# geigerboardschematic.net
KiCad netlist of a schematic drawn in EasyEDA Pro
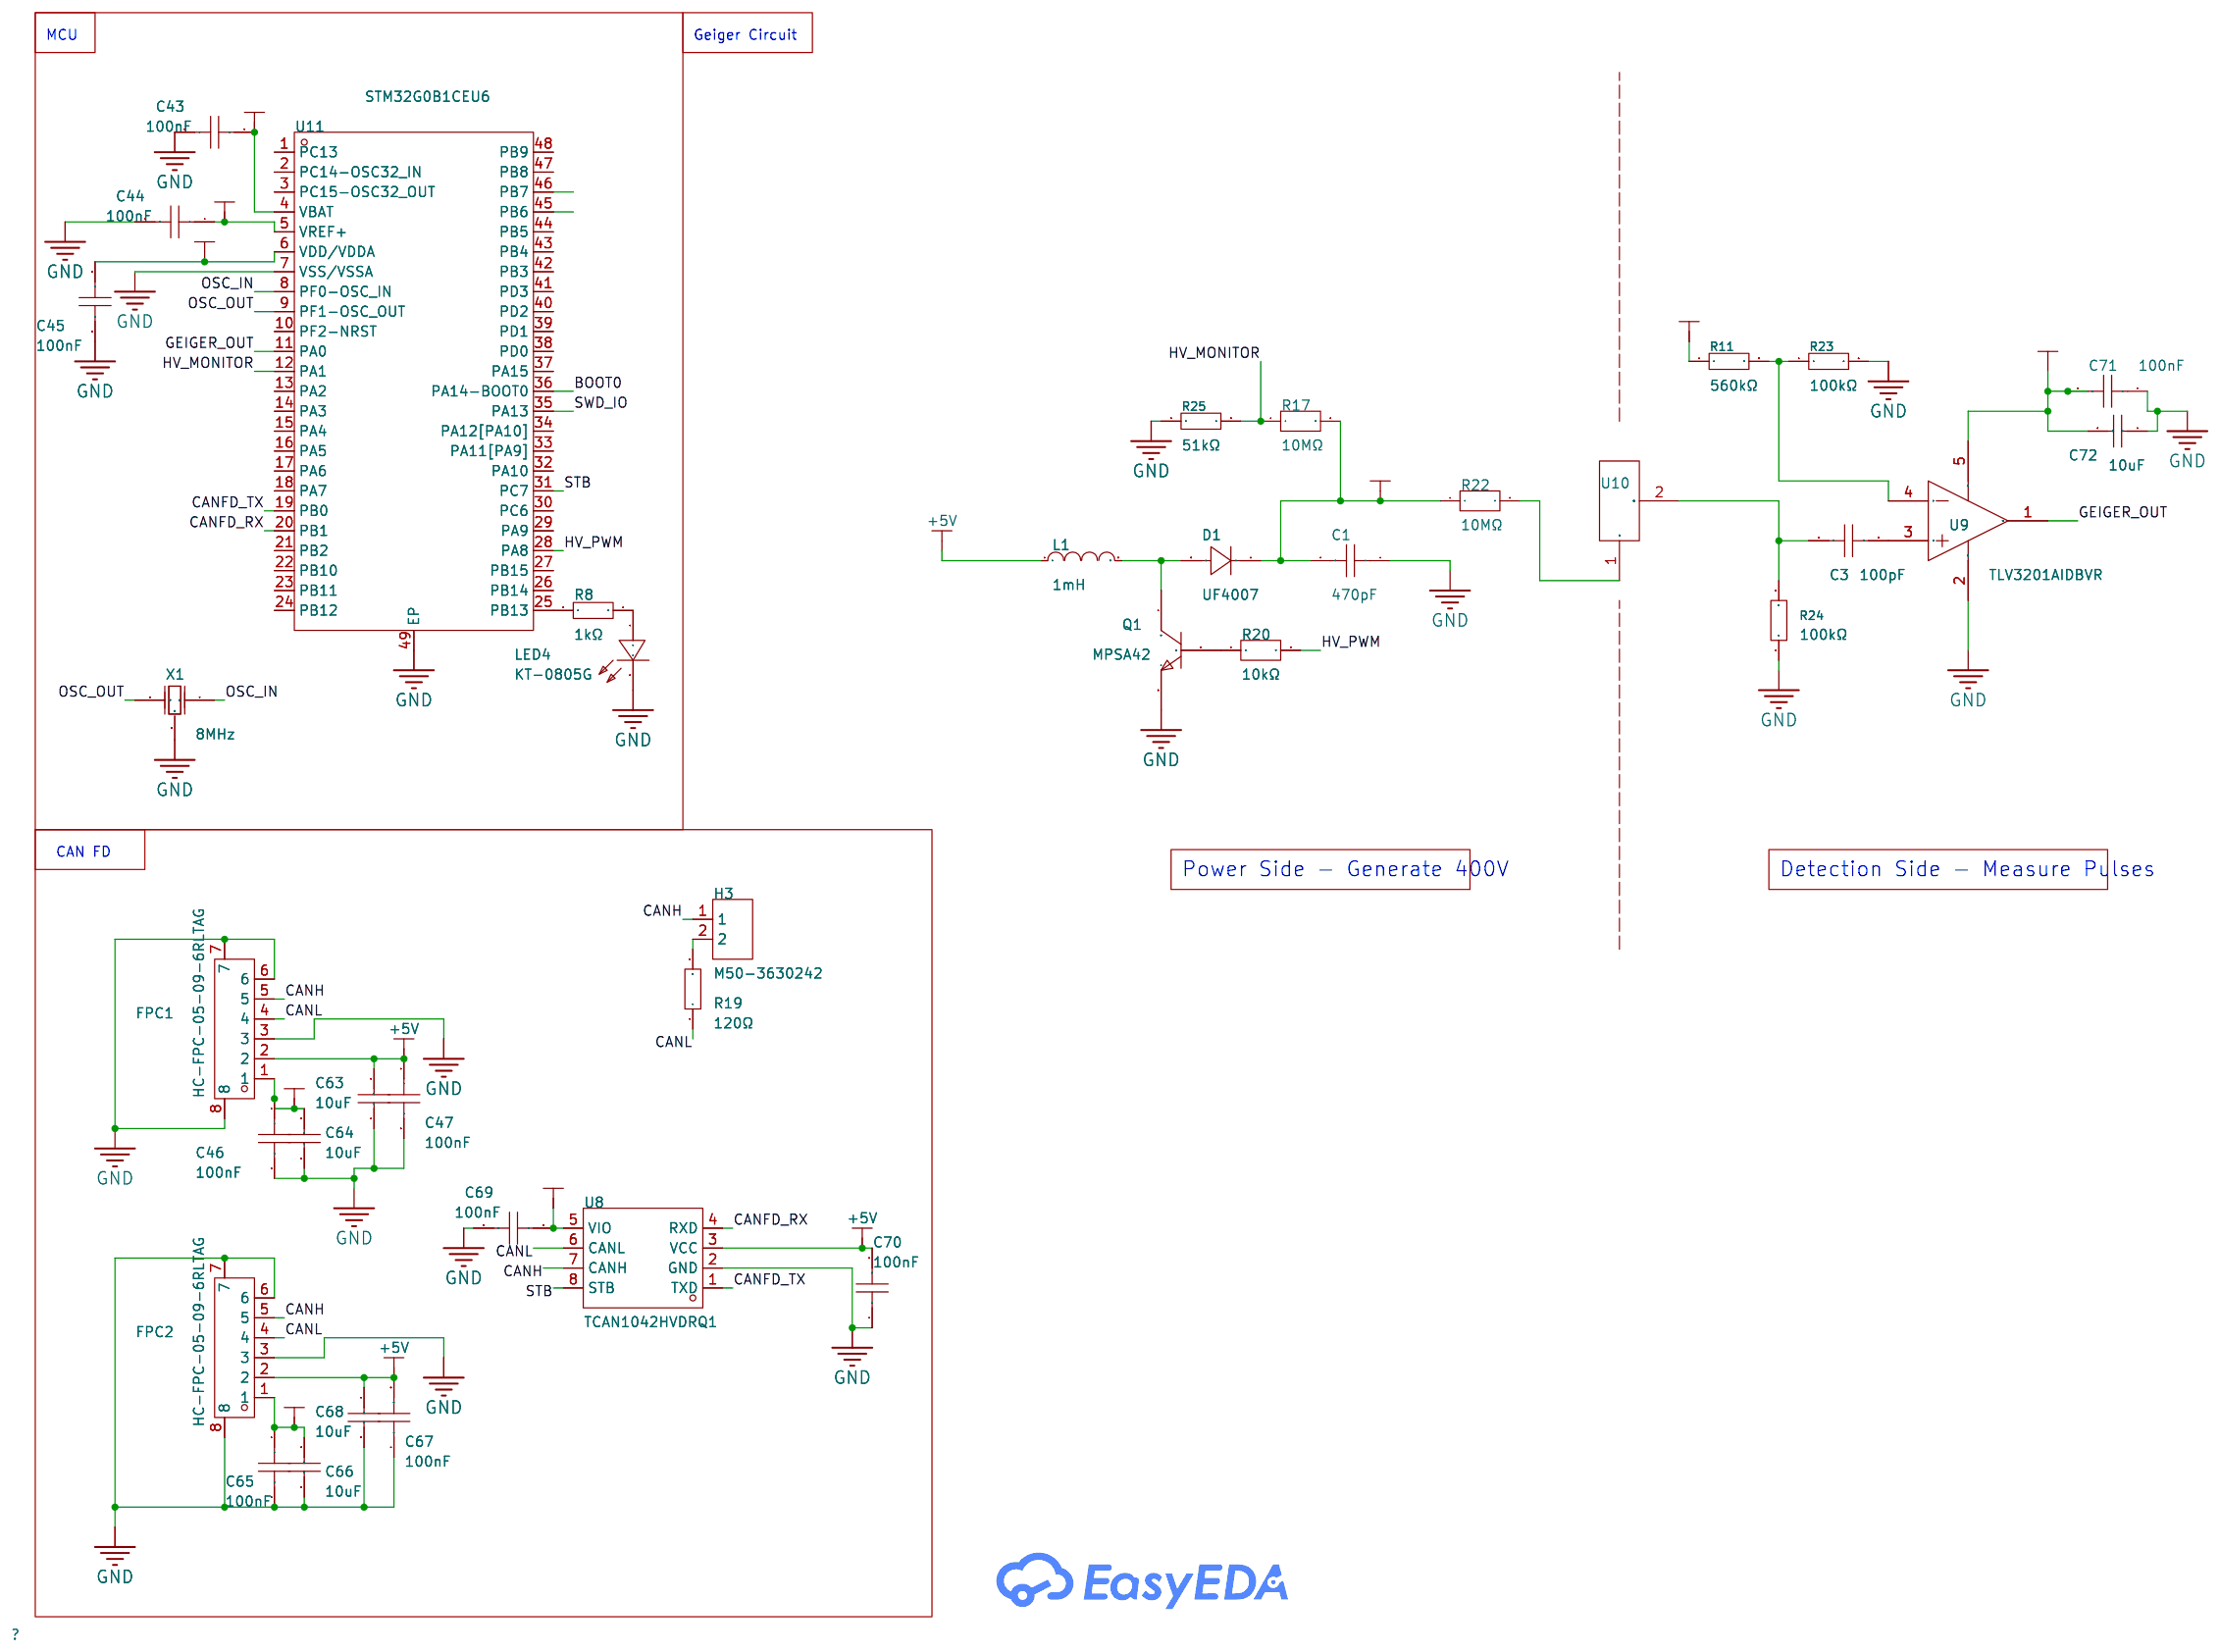
[diagram p0: schematic sheet]

(export (version "E")
  (design (tool "Eeschema 10.0.6"))
  (components
    (comp (ref "C1")
      (value "470pF")
      (footprint "easyedapro:C1111")
      (description "Capacitance:470pF Tolerance:±10% Tolerance:±10% Voltage Rating:630V Temperature Coefficient:C0G")
      (fields (field (name "Manufacturer Part") "VJ1111D471KXLAT") (field (name "Manufacturer") "VISHAY(威世)"))
      (libsource (lib "easyedapro") (part "VJ1111D471KXLAT"))
    )
    (comp (ref "C3")
      (value "100pF")
      (footprint "easyedapro:C1206")
      (fields (field (name "Manufacturer Part") "1206N101J631CT") (field (name "Manufacturer") "Walsin(华新科)"))
      (libsource (lib "easyedapro") (part "1206N101J631CT"))
    )
    (comp (ref "C43")
      (value "100nF")
      (footprint "easyedapro:C0402")
      (description "Capacitance:100nF Tolerance:±10% Tolerance:±10% Voltage Rating:16V Temperature Coefficient:X7R")
      (fields
        (field (name "Manufacturer Part") "CL05B104KO5NNNC")
        (field (name "Manufacturer") "SAMSUNG(三星)")
      )
      (libsource (lib "easyedapro") (part "CL05B104KO5NNNC"))
    )
    (comp (ref "C44")
      (value "100nF")
      (footprint "easyedapro:C0402")
      (description "Capacitance:100nF Tolerance:±10% Tolerance:±10% Voltage Rating:16V Temperature Coefficient:X7R")
      (fields
        (field (name "Manufacturer Part") "CL05B104KO5NNNC")
        (field (name "Manufacturer") "SAMSUNG(三星)")
      )
      (libsource (lib "easyedapro") (part "CL05B104KO5NNNC"))
    )
    (comp (ref "C45")
      (value "100nF")
      (footprint "easyedapro:C0402")
      (description "Capacitance:100nF Tolerance:±10% Tolerance:±10% Voltage Rating:16V Temperature Coefficient:X7R")
      (fields
        (field (name "Manufacturer Part") "CL05B104KO5NNNC")
        (field (name "Manufacturer") "SAMSUNG(三星)")
      )
      (libsource (lib "easyedapro") (part "CL05B104KO5NNNC"))
    )
    (comp (ref "C46")
      (value "100nF")
      (footprint "easyedapro:C0402")
      (description "Capacitance:100nF Tolerance:±10% Tolerance:±10% Voltage Rating:16V Temperature Coefficient:X7R")
      (fields
        (field (name "Manufacturer Part") "CL05B104KO5NNNC")
        (field (name "Manufacturer") "SAMSUNG(三星)")
      )
      (libsource (lib "easyedapro") (part "CL05B104KO5NNNC"))
    )
    (comp (ref "C47")
      (value "100nF")
      (footprint "easyedapro:C0402")
      (description "Capacitance:100nF Tolerance:±10% Tolerance:±10% Voltage Rating:16V Temperature Coefficient:X7R")
      (fields
        (field (name "Manufacturer Part") "CL05B104KO5NNNC")
        (field (name "Manufacturer") "SAMSUNG(三星)")
      )
      (libsource (lib "easyedapro") (part "CL05B104KO5NNNC"))
    )
    (comp (ref "C63")
      (value "10uF")
      (footprint "easyedapro:C0402")
      (description "Capacitance:10uF Tolerance:±20% Tolerance:±20% Voltage Rating:6.3V Temperature Coefficient:X5R")
      (fields
        (field (name "Manufacturer Part") "CL05A106MQ5NUNC")
        (field (name "Manufacturer") "SAMSUNG(三星)")
      )
      (libsource (lib "easyedapro") (part "CL05A106MQ5NUNC"))
    )
    (comp (ref "C64")
      (value "10uF")
      (footprint "easyedapro:C0402")
      (description "Capacitance:10uF Tolerance:±20% Tolerance:±20% Voltage Rating:6.3V Temperature Coefficient:X5R")
      (fields
        (field (name "Manufacturer Part") "CL05A106MQ5NUNC")
        (field (name "Manufacturer") "SAMSUNG(三星)")
      )
      (libsource (lib "easyedapro") (part "CL05A106MQ5NUNC"))
    )
    (comp (ref "C65")
      (value "100nF")
      (footprint "easyedapro:C0402")
      (description "Capacitance:100nF Tolerance:±10% Tolerance:±10% Voltage Rating:16V Temperature Coefficient:X7R")
      (fields
        (field (name "Manufacturer Part") "CL05B104KO5NNNC")
        (field (name "Manufacturer") "SAMSUNG(三星)")
      )
      (libsource (lib "easyedapro") (part "CL05B104KO5NNNC"))
    )
    (comp (ref "C66")
      (value "10uF")
      (footprint "easyedapro:C0402")
      (description "Capacitance:10uF Tolerance:±20% Tolerance:±20% Voltage Rating:6.3V Temperature Coefficient:X5R")
      (fields
        (field (name "Manufacturer Part") "CL05A106MQ5NUNC")
        (field (name "Manufacturer") "SAMSUNG(三星)")
      )
      (libsource (lib "easyedapro") (part "CL05A106MQ5NUNC"))
    )
    (comp (ref "C67")
      (value "100nF")
      (footprint "easyedapro:C0402")
      (description "Capacitance:100nF Tolerance:±10% Tolerance:±10% Voltage Rating:16V Temperature Coefficient:X7R")
      (fields
        (field (name "Manufacturer Part") "CL05B104KO5NNNC")
        (field (name "Manufacturer") "SAMSUNG(三星)")
      )
      (libsource (lib "easyedapro") (part "CL05B104KO5NNNC"))
    )
    (comp (ref "C68")
      (value "10uF")
      (footprint "easyedapro:C0402")
      (description "Capacitance:10uF Tolerance:±20% Tolerance:±20% Voltage Rating:6.3V Temperature Coefficient:X5R")
      (fields
        (field (name "Manufacturer Part") "CL05A106MQ5NUNC")
        (field (name "Manufacturer") "SAMSUNG(三星)")
      )
      (libsource (lib "easyedapro") (part "CL05A106MQ5NUNC"))
    )
    (comp (ref "C69")
      (value "100nF")
      (footprint "easyedapro:C0402")
      (description "Capacitance:100nF Tolerance:±10% Tolerance:±10% Voltage Rating:16V Temperature Coefficient:X7R")
      (fields
        (field (name "Manufacturer Part") "CL05B104KO5NNNC")
        (field (name "Manufacturer") "SAMSUNG(三星)")
      )
      (libsource (lib "easyedapro") (part "CL05B104KO5NNNC"))
    )
    (comp (ref "C70")
      (value "100nF")
      (footprint "easyedapro:C0402")
      (description "Capacitance:100nF Tolerance:±10% Tolerance:±10% Voltage Rating:16V Temperature Coefficient:X7R")
      (fields
        (field (name "Manufacturer Part") "CL05B104KO5NNNC")
        (field (name "Manufacturer") "SAMSUNG(三星)")
      )
      (libsource (lib "easyedapro") (part "CL05B104KO5NNNC"))
    )
    (comp (ref "C71")
      (value "100nF")
      (footprint "easyedapro:C0402")
      (description "Capacitance:100nF Tolerance:±10% Tolerance:±10% Voltage Rating:16V Temperature Coefficient:X7R")
      (fields
        (field (name "Manufacturer Part") "CL05B104KO5NNNC")
        (field (name "Manufacturer") "SAMSUNG(三星)")
      )
      (libsource (lib "easyedapro") (part "CL05B104KO5NNNC"))
    )
    (comp (ref "C72")
      (value "10uF")
      (footprint "easyedapro:C0402")
      (description "Capacitance:10uF Tolerance:±20% Tolerance:±20% Voltage Rating:6.3V Temperature Coefficient:X5R")
      (fields
        (field (name "Manufacturer Part") "CL05A106MQ5NUNC")
        (field (name "Manufacturer") "SAMSUNG(三星)")
      )
      (libsource (lib "easyedapro") (part "CL05A106MQ5NUNC"))
    )
    (comp (ref "D1")
      (value "UF4007")
      (footprint "easyedapro:DO-41_BD2.4-L4.7-P8.70-D0.9-RD")
      (fields (field (name "Manufacturer") "MDD(辰达半导体)"))
      (libsource (lib "easyedapro") (part "UF4007_C960666"))
    )
    (comp (ref "FPC1")
      (value "HC-FPC-05-09-6RLTAG")
      (footprint "easyedapro:FPC-SMD_6P-P0.50_HC-FPC-05-09-6RLTAG")
      (fields (field (name "Manufacturer") "HCTL(华灿天禄)"))
      (libsource (lib "easyedapro") (part "HC-FPC-05-09-6RLTAG"))
    )
    (comp (ref "FPC2")
      (value "HC-FPC-05-09-6RLTAG")
      (footprint "easyedapro:FPC-SMD_6P-P0.50_HC-FPC-05-09-6RLTAG")
      (fields (field (name "Manufacturer") "HCTL(华灿天禄)"))
      (libsource (lib "easyedapro") (part "HC-FPC-05-09-6RLTAG"))
    )
    (comp (ref "H3")
      (value "M50-3630242")
      (footprint "easyedapro:HDR-SMD_2P-P1.27_M50-3630242")
      (fields (field (name "Manufacturer") "Harwin"))
      (libsource (lib "easyedapro") (part "M50-3630242"))
    )
    (comp (ref "L1")
      (value "1mH")
      (footprint "easyedapro:IND-SMD_L5.0-W5.0_FNR50XXS")
      (fields (field (name "Manufacturer Part") "FNR5040S102MT") (field (name "Manufacturer") "cjiang(长江微电)"))
      (libsource (lib "easyedapro") (part "FNR5040S102MT"))
    )
    (comp (ref "LED4")
      (value "KT-0805G")
      (footprint "easyedapro:LED0805-R-RD")
      (fields (field (name "Manufacturer") "KENTO"))
      (libsource (lib "easyedapro") (part "0805G (Green)"))
    )
    (comp (ref "Q1")
      (value "MPSA42")
      (footprint "easyedapro:TO-92-3_L4.8-W3.7-P2.54-R")
      (fields (field (name "Manufacturer") "BLUE ROCKET(蓝箭)"))
      (libsource (lib "easyedapro") (part "MPSA42_C305411"))
    )
    (comp (ref "R8")
      (value "1kΩ")
      (footprint "easyedapro:R0402")
      (fields
        (field (name "Manufacturer Part") "0402WGF1001TCE")
        (field (name "Manufacturer") "UNI-ROYAL(厚声)")
      )
      (libsource (lib "easyedapro") (part "0402WGF1001TCE"))
    )
    (comp (ref "R11")
      (value "560kΩ")
      (footprint "easyedapro:R0402")
      (fields
        (field (name "Manufacturer Part") "0402WGF5603TCE")
        (field (name "Manufacturer") "UNI-ROYAL(厚声)")
      )
      (libsource (lib "easyedapro") (part "0402WGF5603TCE"))
    )
    (comp (ref "R17")
      (value "10MΩ")
      (footprint "easyedapro:R1206")
      (fields (field (name "Manufacturer Part") "KTR18EZPJ106") (field (name "Manufacturer") "ROHM(罗姆)"))
      (libsource (lib "easyedapro") (part "KTR18EZPJ106"))
    )
    (comp (ref "R19")
      (value "120Ω")
      (footprint "easyedapro:R0402")
      (fields
        (field (name "Manufacturer Part") "0402WGF1200TCE")
        (field (name "Manufacturer") "UNI-ROYAL(厚声)")
      )
      (libsource (lib "easyedapro") (part "0402WGF1200TCE"))
    )
    (comp (ref "R20")
      (value "10kΩ")
      (footprint "easyedapro:R0402")
      (fields (field (name "Manufacturer Part") "FRC0402J103 TS") (field (name "Manufacturer") "FOJAN(富捷)"))
      (libsource (lib "easyedapro") (part "FRC0402J103 TS"))
    )
    (comp (ref "R22")
      (value "10MΩ")
      (footprint "easyedapro:R1206")
      (fields (field (name "Manufacturer Part") "KTR18EZPJ106") (field (name "Manufacturer") "ROHM(罗姆)"))
      (libsource (lib "easyedapro") (part "KTR18EZPJ106"))
    )
    (comp (ref "R23")
      (value "100kΩ")
      (footprint "easyedapro:R0402")
      (fields
        (field (name "Manufacturer Part") "0402WGF1003TCE")
        (field (name "Manufacturer") "UNI-ROYAL(厚声)")
      )
      (libsource (lib "easyedapro") (part "0402WGF1003TCE"))
    )
    (comp (ref "R24")
      (value "100kΩ")
      (footprint "easyedapro:R0402")
      (fields
        (field (name "Manufacturer Part") "0402WGF1003TCE")
        (field (name "Manufacturer") "UNI-ROYAL(厚声)")
      )
      (libsource (lib "easyedapro") (part "0402WGF1003TCE"))
    )
    (comp (ref "R25")
      (value "51kΩ")
      (footprint "easyedapro:R0805")
      (fields
        (field (name "Manufacturer Part") "0805W8F5102T5E")
        (field (name "Manufacturer") "UNI-ROYAL(厚声)")
      )
      (libsource (lib "easyedapro") (part "0805W8F5102T5E"))
    )
    (comp (ref "U8")
      (value "TCAN1042HVDRQ1")
      (footprint "easyedapro:SOIC-8_L4.9-W3.9-P1.27-LS6.0-BL")
      (fields (field (name "Manufacturer") "TI(德州仪器)"))
      (libsource (lib "easyedapro") (part "TCAN1042HVDRQ1"))
    )
    (comp (ref "U9")
      (value "TLV3201AIDBVR")
      (footprint "easyedapro:SOT-23-5_L3.0-W1.7-P0.95-LS2.8-BR")
      (fields (field (name "Manufacturer") "TI(德州仪器)"))
      (libsource (lib "easyedapro") (part "TLV3201AIDBVR"))
    )
    (comp (ref "U10")
      (value "SBM-21")
      (footprint "easyedapro:SBM21")
      (libsource (lib "easyedapro") (part "SBM21"))
    )
    (comp (ref "U11")
      (value "STM32G0B1CEU6")
      (footprint "easyedapro:UFQFPN-48_L7.0-W7.0-P0.50-BL-EP")
      (fields (field (name "Manufacturer") "ST(意法半导体)"))
      (libsource (lib "easyedapro") (part "STM32G0B1CEU6"))
    )
    (comp (ref "X1")
      (value "8MHz")
      (footprint "easyedapro:OSC-SMD_3P-L3.2-W1.3-P1.20-L")
      (fields
        (field (name "Manufacturer Part") "CSTNE8M00GH5C000R0")
        (field (name "Manufacturer") "muRata(村田)")
      )
      (libsource (lib "easyedapro") (part "CSTNE8M00GH5C000R0"))
    )
  )
  (nets
    (net (code "1") (name "+5V") (class "Default")
      (node (ref "C47") (pin "1") (pinfunction "1_1") (pintype "unspecified"))
      (node (ref "C63") (pin "2") (pinfunction "2_2") (pintype "input"))
      (node (ref "C67") (pin "2") (pinfunction "2_2") (pintype "unspecified"))
      (node (ref "C68") (pin "1") (pinfunction "1_1") (pintype "input"))
      (node (ref "C70") (pin "2") (pinfunction "2_2") (pintype "unspecified"))
      (node (ref "FPC1") (pin "2") (pinfunction "2_2") (pintype "unspecified"))
      (node (ref "FPC2") (pin "2") (pinfunction "2_2") (pintype "unspecified"))
      (node (ref "L1") (pin "1") (pinfunction "1_1") (pintype "unspecified"))
      (node (ref "U8") (pin "3") (pinfunction "VCC_3") (pintype "unspecified"))
    )
    (net (code "2") (name "+400V") (class "Default")
      (node (ref "C1") (pin "2") (pinfunction "2_2") (pintype "unspecified"))
      (node (ref "D1") (pin "1") (pinfunction "K_1") (pintype "unspecified"))
      (node (ref "R17") (pin "2") (pinfunction "2_2") (pintype "unspecified"))
      (node (ref "R22") (pin "1") (pinfunction "1_1") (pintype "unspecified"))
    )
    (net (code "3") (name "/BOOT0") (class "Default")
      (node (ref "U11") (pin "36") (pinfunction "PA14-BOOT0_36") (pintype "unspecified"))
    )
    (net (code "4") (name "/CANFD_RX") (class "Default")
      (node (ref "U11") (pin "20") (pinfunction "PB1_20") (pintype "unspecified"))
      (node (ref "U8") (pin "4") (pinfunction "RXD_4") (pintype "unspecified"))
    )
    (net (code "5") (name "/CANFD_TX") (class "Default")
      (node (ref "U11") (pin "19") (pinfunction "PB0_19") (pintype "unspecified"))
      (node (ref "U8") (pin "1") (pinfunction "TXD_1") (pintype "unspecified"))
    )
    (net (code "6") (name "/CANH") (class "Default")
      (node (ref "FPC1") (pin "5") (pinfunction "5_5") (pintype "unspecified"))
      (node (ref "FPC2") (pin "5") (pinfunction "5_5") (pintype "unspecified"))
      (node (ref "H3") (pin "1") (pinfunction "1_1") (pintype "unspecified"))
      (node (ref "U8") (pin "7") (pinfunction "CANH_7") (pintype "unspecified"))
    )
    (net (code "7") (name "/CANL") (class "Default")
      (node (ref "FPC1") (pin "4") (pinfunction "4_4") (pintype "unspecified"))
      (node (ref "FPC2") (pin "4") (pinfunction "4_4") (pintype "unspecified"))
      (node (ref "R19") (pin "1") (pinfunction "1_1") (pintype "input"))
      (node (ref "U8") (pin "6") (pinfunction "CANL_6") (pintype "unspecified"))
    )
    (net (code "8") (name "/GEIGER_OUT") (class "Default")
      (node (ref "U11") (pin "11") (pinfunction "PA0_11") (pintype "unspecified"))
      (node (ref "U9") (pin "1") (pinfunction "OUT_1") (pintype "output"))
    )
    (net (code "9") (name "/HV_MONITOR") (class "Default")
      (node (ref "R17") (pin "1") (pinfunction "1_1") (pintype "unspecified"))
      (node (ref "R25") (pin "2") (pinfunction "2_2") (pintype "input"))
      (node (ref "U11") (pin "12") (pinfunction "PA1_12") (pintype "unspecified"))
    )
    (net (code "10") (name "/HV_PWM") (class "Default")
      (node (ref "R20") (pin "2") (pinfunction "2_2") (pintype "unspecified"))
      (node (ref "U11") (pin "28") (pinfunction "PA8_28") (pintype "unspecified"))
    )
    (net (code "11") (name "/OSC_IN") (class "Default")
      (node (ref "U11") (pin "8") (pinfunction "PF0-OSC_IN_8") (pintype "unspecified"))
      (node (ref "X1") (pin "1") (pinfunction "OSC1_1") (pintype "input"))
    )
    (net (code "12") (name "/OSC_OUT") (class "Default")
      (node (ref "U11") (pin "9") (pinfunction "PF1-OSC_OUT_9") (pintype "unspecified"))
      (node (ref "X1") (pin "3") (pinfunction "OSC2_3") (pintype "input"))
    )
    (net (code "13") (name "/STB") (class "Default")
      (node (ref "U11") (pin "31") (pinfunction "PC7_31") (pintype "unspecified"))
      (node (ref "U8") (pin "8") (pinfunction "STB_8") (pintype "unspecified"))
    )
    (net (code "14") (name "/SWD_IO") (class "Default")
      (node (ref "U11") (pin "35") (pinfunction "PA13_35") (pintype "unspecified"))
    )
    (net (code "15") (name "3V3") (class "Default")
      (node (ref "C43") (pin "1") (pinfunction "1_1") (pintype "unspecified"))
      (node (ref "C44") (pin "1") (pinfunction "1_1") (pintype "unspecified"))
      (node (ref "C45") (pin "1") (pinfunction "1_1") (pintype "unspecified"))
      (node (ref "C46") (pin "1") (pinfunction "1_1") (pintype "unspecified"))
      (node (ref "C64") (pin "2") (pinfunction "2_2") (pintype "input"))
      (node (ref "C65") (pin "1") (pinfunction "1_1") (pintype "unspecified"))
      (node (ref "C66") (pin "2") (pinfunction "2_2") (pintype "input"))
      (node (ref "C69") (pin "1") (pinfunction "1_1") (pintype "unspecified"))
      (node (ref "C71") (pin "2") (pinfunction "2_2") (pintype "unspecified"))
      (node (ref "C72") (pin "2") (pinfunction "2_2") (pintype "input"))
      (node (ref "FPC1") (pin "1") (pinfunction "1_1") (pintype "unspecified"))
      (node (ref "FPC2") (pin "1") (pinfunction "1_1") (pintype "unspecified"))
      (node (ref "R11") (pin "1") (pinfunction "1_1") (pintype "input"))
      (node (ref "U11") (pin "4") (pinfunction "VBAT_4") (pintype "unspecified"))
      (node (ref "U11") (pin "5") (pinfunction "VREF+_5") (pintype "unspecified"))
      (node (ref "U11") (pin "6") (pinfunction "VDD/VDDA_6") (pintype "unspecified"))
      (node (ref "U8") (pin "5") (pinfunction "VIO_5") (pintype "unspecified"))
      (node (ref "U9") (pin "5") (pinfunction "VCC_5") (pintype "unspecified"))
    )
    (net (code "16") (name "GND") (class "Default")
      (node (ref "C1") (pin "1") (pinfunction "1_1") (pintype "unspecified"))
      (node (ref "C43") (pin "2") (pinfunction "2_2") (pintype "unspecified"))
      (node (ref "C44") (pin "2") (pinfunction "2_2") (pintype "unspecified"))
      (node (ref "C45") (pin "2") (pinfunction "2_2") (pintype "unspecified"))
      (node (ref "C46") (pin "2") (pinfunction "2_2") (pintype "unspecified"))
      (node (ref "C47") (pin "2") (pinfunction "2_2") (pintype "unspecified"))
      (node (ref "C63") (pin "1") (pinfunction "1_1") (pintype "input"))
      (node (ref "C64") (pin "1") (pinfunction "1_1") (pintype "input"))
      (node (ref "C65") (pin "2") (pinfunction "2_2") (pintype "unspecified"))
      (node (ref "C66") (pin "1") (pinfunction "1_1") (pintype "input"))
      (node (ref "C67") (pin "1") (pinfunction "1_1") (pintype "unspecified"))
      (node (ref "C68") (pin "2") (pinfunction "2_2") (pintype "input"))
      (node (ref "C69") (pin "2") (pinfunction "2_2") (pintype "unspecified"))
      (node (ref "C70") (pin "1") (pinfunction "1_1") (pintype "unspecified"))
      (node (ref "C71") (pin "1") (pinfunction "1_1") (pintype "unspecified"))
      (node (ref "C72") (pin "1") (pinfunction "1_1") (pintype "input"))
      (node (ref "FPC1") (pin "3") (pinfunction "3_3") (pintype "unspecified"))
      (node (ref "FPC1") (pin "6") (pinfunction "6_6") (pintype "unspecified"))
      (node (ref "FPC1") (pin "7") (pinfunction "7_7") (pintype "unspecified"))
      (node (ref "FPC1") (pin "8") (pinfunction "8_8") (pintype "unspecified"))
      (node (ref "FPC2") (pin "3") (pinfunction "3_3") (pintype "unspecified"))
      (node (ref "FPC2") (pin "6") (pinfunction "6_6") (pintype "unspecified"))
      (node (ref "FPC2") (pin "7") (pinfunction "7_7") (pintype "unspecified"))
      (node (ref "FPC2") (pin "8") (pinfunction "8_8") (pintype "unspecified"))
      (node (ref "LED4") (pin "2") (pinfunction "K_2") (pintype "unspecified"))
      (node (ref "Q1") (pin "3") (pinfunction "E_3") (pintype "unspecified"))
      (node (ref "R23") (pin "2") (pinfunction "2_2") (pintype "input"))
      (node (ref "R24") (pin "1") (pinfunction "1_1") (pintype "input"))
      (node (ref "R25") (pin "1") (pinfunction "1_1") (pintype "input"))
      (node (ref "U11") (pin "49") (pinfunction "EP_49") (pintype "unspecified"))
      (node (ref "U11") (pin "7") (pinfunction "VSS/VSSA_7") (pintype "unspecified"))
      (node (ref "U8") (pin "2") (pinfunction "GND_2") (pintype "unspecified"))
      (node (ref "U9") (pin "2") (pinfunction "GND_2") (pintype "unspecified"))
      (node (ref "X1") (pin "2") (pinfunction "GND_2") (pintype "input"))
    )
    (net (code "17") (name "Net-(D1-A)") (class "Default")
      (node (ref "D1") (pin "2") (pinfunction "A_2") (pintype "unspecified"))
      (node (ref "L1") (pin "2") (pinfunction "2_2") (pintype "unspecified"))
      (node (ref "Q1") (pin "1") (pinfunction "C_1") (pintype "unspecified"))
    )
    (net (code "18") (name "Net-(H3-Pad2)") (class "Default")
      (node (ref "H3") (pin "2") (pinfunction "2_2") (pintype "unspecified"))
      (node (ref "R19") (pin "2") (pinfunction "2_2") (pintype "input"))
    )
    (net (code "19") (name "Net-(LED4-A)") (class "Default")
      (node (ref "LED4") (pin "1") (pinfunction "A_1") (pintype "unspecified"))
      (node (ref "R8") (pin "1") (pinfunction "1_1") (pintype "input"))
    )
    (net (code "20") (name "Net-(Q1-B)") (class "Default")
      (node (ref "Q1") (pin "2") (pinfunction "B_2") (pintype "unspecified"))
      (node (ref "R20") (pin "1") (pinfunction "1_1") (pintype "unspecified"))
    )
    (net (code "21") (name "Net-(U9-IN+)") (class "Default")
      (node (ref "C3") (pin "2") (pinfunction "2_2") (pintype "unspecified"))
      (node (ref "U9") (pin "3") (pinfunction "IN+_3") (pintype "unspecified"))
    )
    (net (code "22") (name "Net-(U9-IN-)") (class "Default")
      (node (ref "R11") (pin "2") (pinfunction "2_2") (pintype "input"))
      (node (ref "R23") (pin "1") (pinfunction "1_1") (pintype "input"))
      (node (ref "U9") (pin "4") (pinfunction "IN-_4") (pintype "unspecified"))
    )
    (net (code "23") (name "Net-(U10-Anode)") (class "Default")
      (node (ref "R22") (pin "2") (pinfunction "2_2") (pintype "unspecified"))
      (node (ref "U10") (pin "1") (pinfunction "Anode_1") (pintype "input"))
    )
    (net (code "24") (name "Net-(U10-Cathode)") (class "Default")
      (node (ref "C3") (pin "1") (pinfunction "1_1") (pintype "unspecified"))
      (node (ref "R24") (pin "2") (pinfunction "2_2") (pintype "input"))
      (node (ref "U10") (pin "2") (pinfunction "Cathode_2") (pintype "input"))
    )
    (net (code "25") (name "Net-(U11-PB13)") (class "Default")
      (node (ref "R8") (pin "2") (pinfunction "2_2") (pintype "input"))
      (node (ref "U11") (pin "25") (pinfunction "PB13_25") (pintype "unspecified"))
    )
    (net (code "26") (name "unconnected-(U11-PA2-Pad13)") (class "Default")
      (node (ref "U11") (pin "13") (pinfunction "PA2_13") (pintype "unspecified"))
    )
    (net (code "27") (name "unconnected-(U11-PA3-Pad14)") (class "Default")
      (node (ref "U11") (pin "14") (pinfunction "PA3_14") (pintype "unspecified"))
    )
    (net (code "28") (name "unconnected-(U11-PA4-Pad15)") (class "Default")
      (node (ref "U11") (pin "15") (pinfunction "PA4_15") (pintype "unspecified"))
    )
    (net (code "29") (name "unconnected-(U11-PA5-Pad16)") (class "Default")
      (node (ref "U11") (pin "16") (pinfunction "PA5_16") (pintype "unspecified"))
    )
    (net (code "30") (name "unconnected-(U11-PA6-Pad17)") (class "Default")
      (node (ref "U11") (pin "17") (pinfunction "PA6_17") (pintype "unspecified"))
    )
    (net (code "31") (name "unconnected-(U11-PA7-Pad18)") (class "Default")
      (node (ref "U11") (pin "18") (pinfunction "PA7_18") (pintype "unspecified"))
    )
    (net (code "32") (name "unconnected-(U11-PA9-Pad29)") (class "Default")
      (node (ref "U11") (pin "29") (pinfunction "PA9_29") (pintype "unspecified"))
    )
    (net (code "33") (name "unconnected-(U11-PA10-Pad32)") (class "Default")
      (node (ref "U11") (pin "32") (pinfunction "PA10_32") (pintype "unspecified"))
    )
    (net (code "34") (name "unconnected-(U11-PA11[PA9]-Pad33)") (class "Default")
      (node (ref "U11") (pin "33") (pinfunction "PA11[PA9]_33") (pintype "unspecified"))
    )
    (net (code "35") (name "unconnected-(U11-PA12[PA10]-Pad34)") (class "Default")
      (node (ref "U11") (pin "34") (pinfunction "PA12[PA10]_34") (pintype "unspecified"))
    )
    (net (code "36") (name "unconnected-(U11-PA15-Pad37)") (class "Default")
      (node (ref "U11") (pin "37") (pinfunction "PA15_37") (pintype "unspecified"))
    )
    (net (code "37") (name "unconnected-(U11-PB2-Pad21)") (class "Default")
      (node (ref "U11") (pin "21") (pinfunction "PB2_21") (pintype "unspecified"))
    )
    (net (code "38") (name "unconnected-(U11-PB3-Pad42)") (class "Default")
      (node (ref "U11") (pin "42") (pinfunction "PB3_42") (pintype "unspecified"))
    )
    (net (code "39") (name "unconnected-(U11-PB4-Pad43)") (class "Default")
      (node (ref "U11") (pin "43") (pinfunction "PB4_43") (pintype "unspecified"))
    )
    (net (code "40") (name "unconnected-(U11-PB5-Pad44)") (class "Default")
      (node (ref "U11") (pin "44") (pinfunction "PB5_44") (pintype "unspecified"))
    )
    (net (code "41") (name "unconnected-(U11-PB6-Pad45)") (class "Default")
      (node (ref "U11") (pin "45") (pinfunction "PB6_45") (pintype "unspecified"))
    )
    (net (code "42") (name "unconnected-(U11-PB7-Pad46)") (class "Default")
      (node (ref "U11") (pin "46") (pinfunction "PB7_46") (pintype "unspecified"))
    )
    (net (code "43") (name "unconnected-(U11-PB8-Pad47)") (class "Default")
      (node (ref "U11") (pin "47") (pinfunction "PB8_47") (pintype "unspecified"))
    )
    (net (code "44") (name "unconnected-(U11-PB9-Pad48)") (class "Default")
      (node (ref "U11") (pin "48") (pinfunction "PB9_48") (pintype "unspecified"))
    )
    (net (code "45") (name "unconnected-(U11-PB10-Pad22)") (class "Default")
      (node (ref "U11") (pin "22") (pinfunction "PB10_22") (pintype "unspecified"))
    )
    (net (code "46") (name "unconnected-(U11-PB11-Pad23)") (class "Default")
      (node (ref "U11") (pin "23") (pinfunction "PB11_23") (pintype "unspecified"))
    )
    (net (code "47") (name "unconnected-(U11-PB12-Pad24)") (class "Default")
      (node (ref "U11") (pin "24") (pinfunction "PB12_24") (pintype "unspecified"))
    )
    (net (code "48") (name "unconnected-(U11-PB14-Pad26)") (class "Default")
      (node (ref "U11") (pin "26") (pinfunction "PB14_26") (pintype "unspecified"))
    )
    (net (code "49") (name "unconnected-(U11-PB15-Pad27)") (class "Default")
      (node (ref "U11") (pin "27") (pinfunction "PB15_27") (pintype "unspecified"))
    )
    (net (code "50") (name "unconnected-(U11-PC6-Pad30)") (class "Default")
      (node (ref "U11") (pin "30") (pinfunction "PC6_30") (pintype "unspecified"))
    )
    (net (code "51") (name "unconnected-(U11-PC13-Pad1)") (class "Default")
      (node (ref "U11") (pin "1") (pinfunction "PC13_1") (pintype "unspecified"))
    )
    (net (code "52") (name "unconnected-(U11-PC14-OSC32_IN-Pad2)") (class "Default")
      (node (ref "U11") (pin "2") (pinfunction "PC14-OSC32_IN_2") (pintype "unspecified"))
    )
    (net (code "53") (name "unconnected-(U11-PC15-OSC32_OUT-Pad3)") (class "Default")
      (node (ref "U11") (pin "3") (pinfunction "PC15-OSC32_OUT_3") (pintype "unspecified"))
    )
    (net (code "54") (name "unconnected-(U11-PD0-Pad38)") (class "Default")
      (node (ref "U11") (pin "38") (pinfunction "PD0_38") (pintype "unspecified"))
    )
    (net (code "55") (name "unconnected-(U11-PD1-Pad39)") (class "Default")
      (node (ref "U11") (pin "39") (pinfunction "PD1_39") (pintype "unspecified"))
    )
    (net (code "56") (name "unconnected-(U11-PD2-Pad40)") (class "Default")
      (node (ref "U11") (pin "40") (pinfunction "PD2_40") (pintype "unspecified"))
    )
    (net (code "57") (name "unconnected-(U11-PD3-Pad41)") (class "Default")
      (node (ref "U11") (pin "41") (pinfunction "PD3_41") (pintype "unspecified"))
    )
    (net (code "58") (name "unconnected-(U11-PF2-NRST-Pad10)") (class "Default")
      (node (ref "U11") (pin "10") (pinfunction "PF2-NRST_10") (pintype "unspecified"))
    )
  )
)
